# frontpanel-hw.net
KiCad netlist of a schematic drawn in Altium Designer
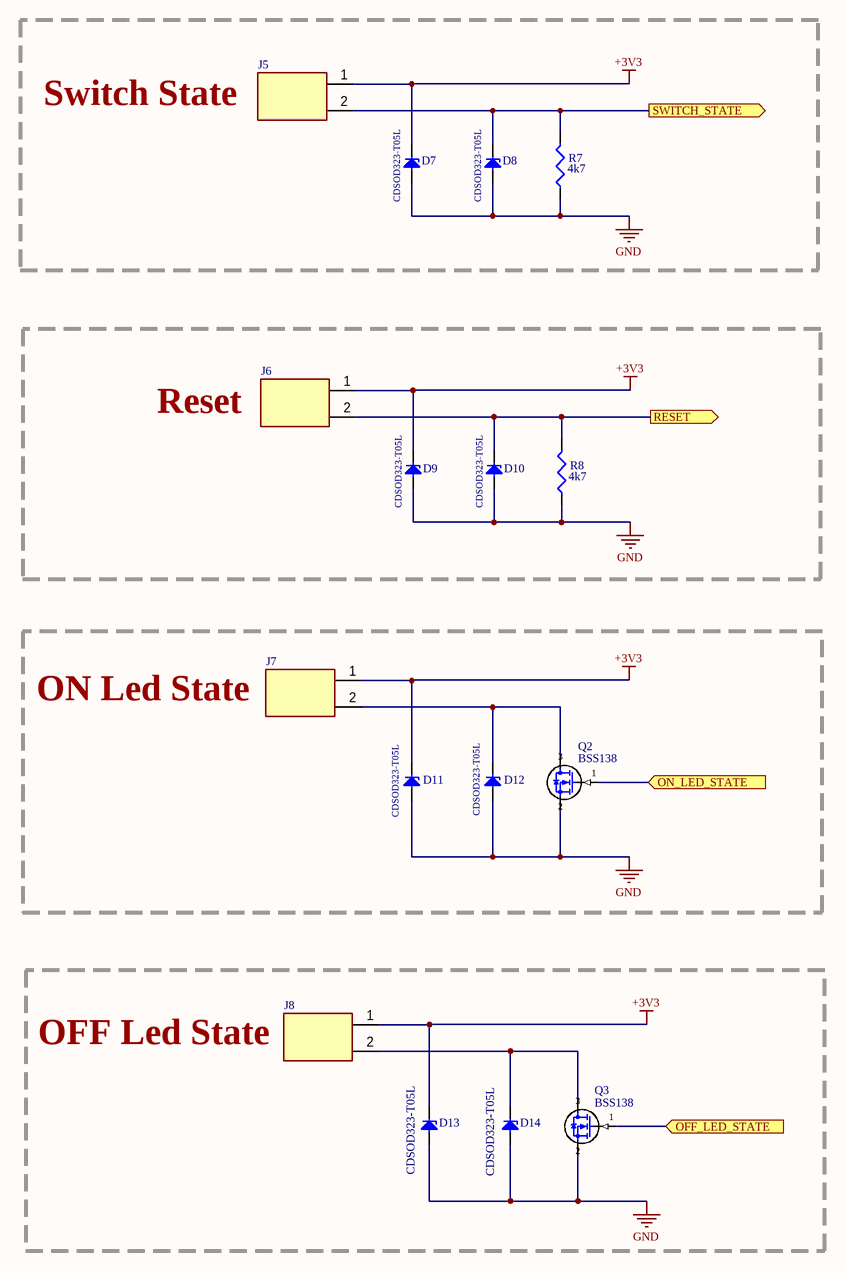
[diagram p0: frontpanel-hw.SchDoc]

(export (version "E")
  (design (tool "Eeschema 10.0.6"))
  (components
    (comp (ref "D7")
      (value "CDSOD323-T05L")
      (footprint "SOD-323")
      (description "Unidirectional TVS Diode")
      (libsource (lib "acopians-powerspy-monitoring-hw-library-schematic") (part "CDSOD323-T05L"))
    )
    (comp (ref "D8")
      (value "CDSOD323-T05L")
      (footprint "SOD-323")
      (description "Unidirectional TVS Diode")
      (libsource (lib "acopians-powerspy-monitoring-hw-library-schematic") (part "CDSOD323-T05L"))
    )
    (comp (ref "D9")
      (value "CDSOD323-T05L")
      (footprint "SOD-323")
      (description "Unidirectional TVS Diode")
      (libsource (lib "acopians-powerspy-monitoring-hw-library-schematic") (part "CDSOD323-T05L"))
    )
    (comp (ref "D10")
      (value "CDSOD323-T05L")
      (footprint "SOD-323")
      (description "Unidirectional TVS Diode")
      (libsource (lib "acopians-powerspy-monitoring-hw-library-schematic") (part "CDSOD323-T05L"))
    )
    (comp (ref "D11")
      (value "CDSOD323-T05L")
      (footprint "SOD-323")
      (description "Unidirectional TVS Diode")
      (libsource (lib "acopians-powerspy-monitoring-hw-library-schematic") (part "CDSOD323-T05L"))
    )
    (comp (ref "D12")
      (value "CDSOD323-T05L")
      (footprint "SOD-323")
      (description "Unidirectional TVS Diode")
      (libsource (lib "acopians-powerspy-monitoring-hw-library-schematic") (part "CDSOD323-T05L"))
    )
    (comp (ref "D13")
      (value "CDSOD323-T05L")
      (footprint "SOD-323")
      (description "Unidirectional TVS Diode")
      (libsource (lib "acopians-powerspy-monitoring-hw-library-schematic") (part "CDSOD323-T05L"))
    )
    (comp (ref "D14")
      (value "CDSOD323-T05L")
      (footprint "SOD-323")
      (description "Unidirectional TVS Diode")
      (libsource (lib "acopians-powerspy-monitoring-hw-library-schematic") (part "CDSOD323-T05L"))
    )
    (comp (ref "J5")
      (value "+15VDC Connector")
      (footprint "+15VDC Connector")
      (libsource (lib "acopians-powerspy-monitoring-hw-library-schematic") (part "+15VDC Connector"))
    )
    (comp (ref "J6")
      (value "+15VDC Connector")
      (footprint "+15VDC Connector")
      (libsource (lib "acopians-powerspy-monitoring-hw-library-schematic") (part "+15VDC Connector"))
    )
    (comp (ref "J7")
      (value "+15VDC Connector")
      (footprint "+15VDC Connector")
      (libsource (lib "acopians-powerspy-monitoring-hw-library-schematic") (part "+15VDC Connector"))
    )
    (comp (ref "J8")
      (value "+15VDC Connector")
      (footprint "+15VDC Connector")
      (libsource (lib "acopians-powerspy-monitoring-hw-library-schematic") (part "+15VDC Connector"))
    )
    (comp (ref "Q2")
      (value "BSS138")
      (footprint "SOT_23_3")
      (description "MOSFET N-Channel")
      (libsource (lib "acopians-powerspy-monitoring-hw-library-schematic") (part "BSS138"))
    )
    (comp (ref "Q3")
      (value "BSS138")
      (footprint "SOT_23_3")
      (description "MOSFET N-Channel")
      (libsource (lib "acopians-powerspy-monitoring-hw-library-schematic") (part "BSS138"))
    )
    (comp (ref "R7")
      (value "4k7")
      (footprint "Resistor 0805")
      (description "Size 0805")
      (libsource (lib "acopians-powerspy-monitoring-hw-library-schematic") (part "Resistor 4k7"))
    )
    (comp (ref "R8")
      (value "4k7")
      (footprint "Resistor 0805")
      (description "Size 0805")
      (libsource (lib "acopians-powerspy-monitoring-hw-library-schematic") (part "Resistor 4k7"))
    )
  )
  (nets
    (net (code "1") (name "+3V3") (class "Default")
      (node (ref "D11") (pin "1") (pintype "passive"))
      (node (ref "D13") (pin "1") (pintype "passive"))
      (node (ref "D7") (pin "1") (pintype "passive"))
      (node (ref "D9") (pin "1") (pintype "passive"))
      (node (ref "J5") (pin "1") (pinfunction "1_1") (pintype "passive"))
      (node (ref "J6") (pin "1") (pinfunction "1_1") (pintype "passive"))
      (node (ref "J7") (pin "1") (pinfunction "1_1") (pintype "passive"))
      (node (ref "J8") (pin "1") (pinfunction "1_1") (pintype "passive"))
    )
    (net (code "2") (name "/OFF_LED_STATE") (class "Default")
      (node (ref "Q3") (pin "1") (pinfunction "G_1") (pintype "input"))
    )
    (net (code "3") (name "/ON_LED_STATE") (class "Default")
      (node (ref "Q2") (pin "1") (pinfunction "G_1") (pintype "input"))
    )
    (net (code "4") (name "/RESET") (class "Default")
      (node (ref "D10") (pin "1") (pintype "passive"))
      (node (ref "J6") (pin "2") (pinfunction "2_2") (pintype "passive"))
      (node (ref "R8") (pin "2") (pinfunction "2_2") (pintype "passive"))
    )
    (net (code "5") (name "/SWITCH_STATE") (class "Default")
      (node (ref "D8") (pin "1") (pintype "passive"))
      (node (ref "J5") (pin "2") (pinfunction "2_2") (pintype "passive"))
      (node (ref "R7") (pin "2") (pinfunction "2_2") (pintype "passive"))
    )
    (net (code "6") (name "GND") (class "Default")
      (node (ref "D10") (pin "2") (pintype "passive"))
      (node (ref "D11") (pin "2") (pintype "passive"))
      (node (ref "D12") (pin "2") (pintype "passive"))
      (node (ref "D13") (pin "2") (pintype "passive"))
      (node (ref "D14") (pin "2") (pintype "passive"))
      (node (ref "D7") (pin "2") (pintype "passive"))
      (node (ref "D8") (pin "2") (pintype "passive"))
      (node (ref "D9") (pin "2") (pintype "passive"))
      (node (ref "Q2") (pin "2") (pinfunction "S_2") (pintype "passive"))
      (node (ref "Q3") (pin "2") (pinfunction "S_2") (pintype "passive"))
      (node (ref "R7") (pin "1") (pinfunction "1_1") (pintype "passive"))
      (node (ref "R8") (pin "1") (pinfunction "1_1") (pintype "passive"))
    )
    (net (code "7") (name "Net-(Q2-D)") (class "Default")
      (node (ref "D12") (pin "1") (pintype "passive"))
      (node (ref "J7") (pin "2") (pinfunction "2_2") (pintype "passive"))
      (node (ref "Q2") (pin "3") (pinfunction "D_3") (pintype "passive"))
    )
    (net (code "8") (name "Net-(Q3-D)") (class "Default")
      (node (ref "D14") (pin "1") (pintype "passive"))
      (node (ref "J8") (pin "2") (pinfunction "2_2") (pintype "passive"))
      (node (ref "Q3") (pin "3") (pinfunction "D_3") (pintype "passive"))
    )
  )
)
